# FOTA_LED_Driver.net
KiCad netlist of a schematic drawn in Altium Designer
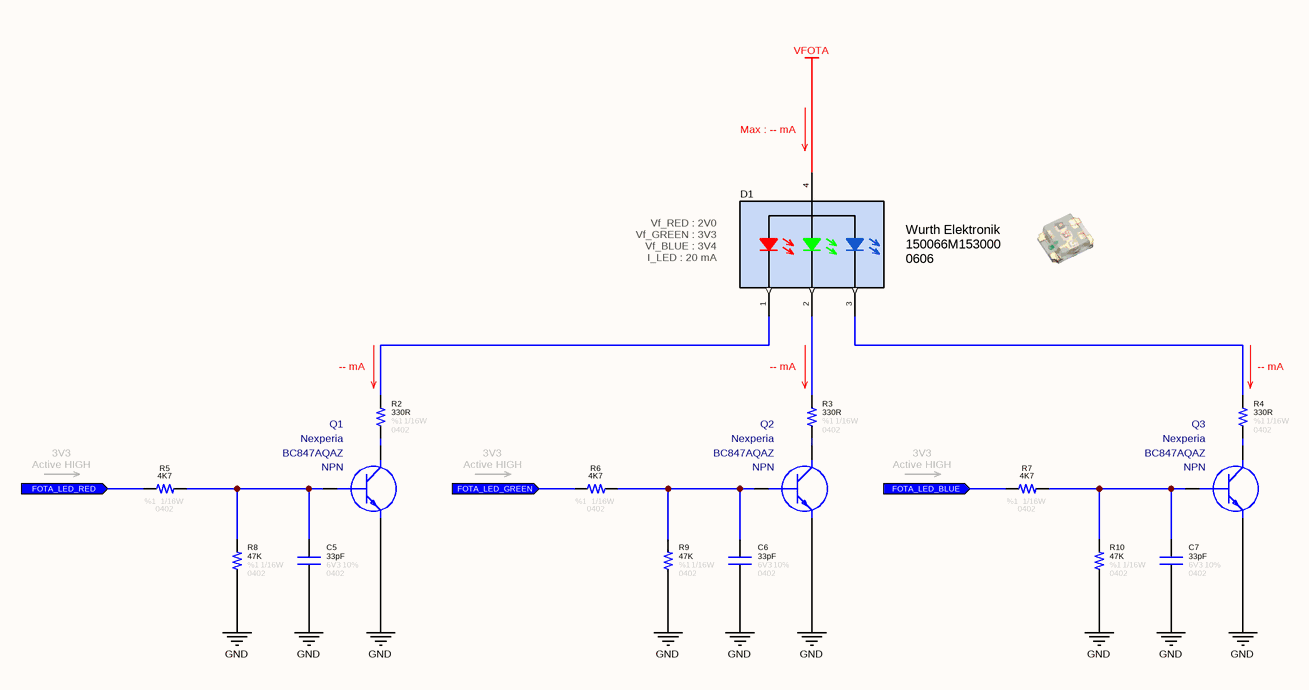
[diagram p0: FOTA LED Driver.SchDoc]

(export (version "E")
  (design (tool "Eeschema 10.0.6"))
  (components
    (comp (ref "C5")
      (value "33pF")
      (footprint "CAPACITOR_0402")
      (description "Capacitor - 33pF [0402] (Ceramic)")
      (fields
        (field (name "MANUFACTURER PART NUMBER") "C0402C330J9RACAUTO")
        (field (name "TOLERANCE") "10%")
        (field (name "CASE") "0402")
        (field (name "VOLTAGE") "6V3")
      )
      (libsource (lib "P101DA_Library") (part "Capacitor - 33pF [0402-6V3]"))
    )
    (comp (ref "C6")
      (value "33pF")
      (footprint "CAPACITOR_0402")
      (description "Capacitor - 33pF [0402] (Ceramic)")
      (fields
        (field (name "MANUFACTURER PART NUMBER") "C0402C330J9RACAUTO")
        (field (name "TOLERANCE") "10%")
        (field (name "CASE") "0402")
        (field (name "VOLTAGE") "6V3")
      )
      (libsource (lib "P101DA_Library") (part "Capacitor - 33pF [0402-6V3]"))
    )
    (comp (ref "C7")
      (value "33pF")
      (footprint "CAPACITOR_0402")
      (description "Capacitor - 33pF [0402] (Ceramic)")
      (fields
        (field (name "MANUFACTURER PART NUMBER") "C0402C330J9RACAUTO")
        (field (name "TOLERANCE") "10%")
        (field (name "CASE") "0402")
        (field (name "VOLTAGE") "6V3")
      )
      (libsource (lib "P101DA_Library") (part "Capacitor - 33pF [0402-6V3]"))
    )
    (comp (ref "D1")
      (value "150066M153000")
      (footprint "Wurth_0606")
      (description "LED RGB DIFFUSED SMD")
      (fields
        (field (name "MANUFACTURER NAME") "Wurth Elektronik")
        (field (name "MANUFACTURER PART NUMBER") "150066M153000")
        (field (name "CASE") "0606")
      )
      (libsource (lib "P101DA_Library") (part "Diode - LED-RGB"))
    )
    (comp (ref "Q1")
      (value "BC847AQAZ")
      (footprint "SOT1215")
      (description "Bipolar NPN Transistors")
      (fields
        (field (name "MANUFACTURER NAME") "Nexperia")
        (field (name "MANUFACTURER PART NUMBER") "BC847AQAZ")
        (field (name "POLARITY") "NPN")
      )
      (libsource (lib "P101DA_Library") (part "Transistor - BC847"))
    )
    (comp (ref "Q2")
      (value "BC847AQAZ")
      (footprint "SOT1215")
      (description "Bipolar NPN Transistors")
      (fields
        (field (name "MANUFACTURER NAME") "Nexperia")
        (field (name "MANUFACTURER PART NUMBER") "BC847AQAZ")
        (field (name "POLARITY") "NPN")
      )
      (libsource (lib "P101DA_Library") (part "Transistor - BC847"))
    )
    (comp (ref "Q3")
      (value "BC847AQAZ")
      (footprint "SOT1215")
      (description "Bipolar NPN Transistors")
      (fields
        (field (name "MANUFACTURER NAME") "Nexperia")
        (field (name "MANUFACTURER PART NUMBER") "BC847AQAZ")
        (field (name "POLARITY") "NPN")
      )
      (libsource (lib "P101DA_Library") (part "Transistor - BC847"))
    )
    (comp (ref "R2")
      (value "330R")
      (footprint "RESISTOR_0402")
      (description "Thick Film Resistors - SMD 1/16 W 330 Ohm 1%")
      (fields
        (field (name "MANUFACTURER PART NUMBER") "CRCW0402330RFKED")
        (field (name "CASE") "0402")
        (field (name "TOLERANCE") "%1")
        (field (name "POWER") "1/16W")
        (field (name "Comment") "330R - 0402 - %1 - 1/16W")
      )
      (libsource (lib "P101DA_Library") (part "Resistor - 330R [0402]"))
    )
    (comp (ref "R3")
      (value "330R")
      (footprint "RESISTOR_0402")
      (description "Thick Film Resistors - SMD 1/16 W 330 Ohm 1%")
      (fields
        (field (name "MANUFACTURER PART NUMBER") "CRCW0402330RFKED")
        (field (name "CASE") "0402")
        (field (name "TOLERANCE") "%1")
        (field (name "POWER") "1/16W")
        (field (name "Comment") "330R - 0402 - %1 - 1/16W")
      )
      (libsource (lib "P101DA_Library") (part "Resistor - 330R [0402]"))
    )
    (comp (ref "R4")
      (value "330R")
      (footprint "RESISTOR_0402")
      (description "Thick Film Resistors - SMD 1/16 W 330 Ohm 1%")
      (fields
        (field (name "MANUFACTURER PART NUMBER") "CRCW0402330RFKED")
        (field (name "CASE") "0402")
        (field (name "TOLERANCE") "%1")
        (field (name "POWER") "1/16W")
        (field (name "Comment") "330R - 0402 - %1 - 1/16W")
      )
      (libsource (lib "P101DA_Library") (part "Resistor - 330R [0402]"))
    )
    (comp (ref "R5")
      (value "4K7")
      (footprint "RESISTOR_0402")
      (description "Thick Film Resistors - SMD 1/16 W 4.7 KOhm 1%")
      (fields
        (field (name "MANUFACTURER PART NUMBER") "CRCW04024K70FKED")
        (field (name "TOLERANCE") "%1")
        (field (name "CASE") "0402")
        (field (name "POWER") "1/16W")
        (field (name "Comment") "4K7 - 0402 - %1 - 1/16W")
      )
      (libsource (lib "P101DA_Library") (part "Resistor - 4K7 [0402]"))
    )
    (comp (ref "R6")
      (value "4K7")
      (footprint "RESISTOR_0402")
      (description "Thick Film Resistors - SMD 1/16 W 4.7 KOhm 1%")
      (fields
        (field (name "MANUFACTURER PART NUMBER") "CRCW04024K70FKED")
        (field (name "TOLERANCE") "%1")
        (field (name "CASE") "0402")
        (field (name "POWER") "1/16W")
        (field (name "Comment") "4K7 - 0402 - %1 - 1/16W")
      )
      (libsource (lib "P101DA_Library") (part "Resistor - 4K7 [0402]"))
    )
    (comp (ref "R7")
      (value "4K7")
      (footprint "RESISTOR_0402")
      (description "Thick Film Resistors - SMD 1/16 W 4.7 KOhm 1%")
      (fields
        (field (name "MANUFACTURER PART NUMBER") "CRCW04024K70FKED")
        (field (name "TOLERANCE") "%1")
        (field (name "CASE") "0402")
        (field (name "POWER") "1/16W")
        (field (name "Comment") "4K7 - 0402 - %1 - 1/16W")
      )
      (libsource (lib "P101DA_Library") (part "Resistor - 4K7 [0402]"))
    )
    (comp (ref "R8")
      (value "47K")
      (footprint "RESISTOR_0402")
      (description "Thick Film Resistors - SMD 1/16 W 47 KOhm 1%")
      (fields
        (field (name "MANUFACTURER PART NUMBER") "CRCW040247K0FKED")
        (field (name "TOLERANCE") "%1")
        (field (name "CASE") "0402")
        (field (name "POWER") "1/16W")
        (field (name "Comment") "47K - 0402 - %1 - 1/16W")
      )
      (libsource (lib "P101DA_Library") (part "Resistor - 47K [0402]"))
    )
    (comp (ref "R9")
      (value "47K")
      (footprint "RESISTOR_0402")
      (description "Thick Film Resistors - SMD 1/16 W 47 KOhm 1%")
      (fields
        (field (name "MANUFACTURER PART NUMBER") "CRCW040247K0FKED")
        (field (name "TOLERANCE") "%1")
        (field (name "CASE") "0402")
        (field (name "POWER") "1/16W")
        (field (name "Comment") "47K - 0402 - %1 - 1/16W")
      )
      (libsource (lib "P101DA_Library") (part "Resistor - 47K [0402]"))
    )
    (comp (ref "R10")
      (value "47K")
      (footprint "RESISTOR_0402")
      (description "Thick Film Resistors - SMD 1/16 W 47 KOhm 1%")
      (fields
        (field (name "MANUFACTURER PART NUMBER") "CRCW040247K0FKED")
        (field (name "TOLERANCE") "%1")
        (field (name "CASE") "0402")
        (field (name "POWER") "1/16W")
        (field (name "Comment") "47K - 0402 - %1 - 1/16W")
      )
      (libsource (lib "P101DA_Library") (part "Resistor - 47K [0402]"))
    )
  )
  (nets
    (net (code "1") (name "/FOTA_LED_BLUE") (class "Default")
      (node (ref "R7") (pin "2") (pinfunction "2_2") (pintype "passive"))
    )
    (net (code "2") (name "/FOTA_LED_GREEN") (class "Default")
      (node (ref "R6") (pin "2") (pinfunction "2_2") (pintype "passive"))
    )
    (net (code "3") (name "/FOTA_LED_RED") (class "Default")
      (node (ref "R5") (pin "2") (pinfunction "2_2") (pintype "passive"))
    )
    (net (code "4") (name "GND") (class "Default")
      (node (ref "C5") (pin "1") (pinfunction "1_1") (pintype "passive"))
      (node (ref "C6") (pin "1") (pinfunction "1_1") (pintype "passive"))
      (node (ref "C7") (pin "1") (pinfunction "1_1") (pintype "passive"))
      (node (ref "Q1") (pin "2") (pinfunction "E_2") (pintype "passive"))
      (node (ref "Q2") (pin "2") (pinfunction "E_2") (pintype "passive"))
      (node (ref "Q3") (pin "2") (pinfunction "E_2") (pintype "passive"))
      (node (ref "R10") (pin "1") (pinfunction "1_1") (pintype "passive"))
      (node (ref "R8") (pin "1") (pinfunction "1_1") (pintype "passive"))
      (node (ref "R9") (pin "1") (pinfunction "1_1") (pintype "passive"))
    )
    (net (code "5") (name "Net-(D1-Pad1)") (class "Default")
      (node (ref "D1") (pin "1") (pinfunction "1_1") (pintype "output"))
      (node (ref "R2") (pin "2") (pinfunction "2_2") (pintype "passive"))
    )
    (net (code "6") (name "Net-(D1-Pad2)") (class "Default")
      (node (ref "D1") (pin "2") (pinfunction "2_2") (pintype "output"))
      (node (ref "R3") (pin "2") (pinfunction "2_2") (pintype "passive"))
    )
    (net (code "7") (name "Net-(D1-Pad3)") (class "Default")
      (node (ref "D1") (pin "3") (pinfunction "3_3") (pintype "output"))
      (node (ref "R4") (pin "2") (pinfunction "2_2") (pintype "passive"))
    )
    (net (code "8") (name "Net-(Q1-B)") (class "Default")
      (node (ref "C5") (pin "2") (pinfunction "2_2") (pintype "passive"))
      (node (ref "Q1") (pin "1") (pinfunction "B_1") (pintype "passive"))
      (node (ref "R5") (pin "1") (pinfunction "1_1") (pintype "passive"))
      (node (ref "R8") (pin "2") (pinfunction "2_2") (pintype "passive"))
    )
    (net (code "9") (name "Net-(Q1-C)") (class "Default")
      (node (ref "Q1") (pin "3") (pinfunction "C_3") (pintype "passive"))
      (node (ref "R2") (pin "1") (pinfunction "1_1") (pintype "passive"))
    )
    (net (code "10") (name "Net-(Q2-B)") (class "Default")
      (node (ref "C6") (pin "2") (pinfunction "2_2") (pintype "passive"))
      (node (ref "Q2") (pin "1") (pinfunction "B_1") (pintype "passive"))
      (node (ref "R6") (pin "1") (pinfunction "1_1") (pintype "passive"))
      (node (ref "R9") (pin "2") (pinfunction "2_2") (pintype "passive"))
    )
    (net (code "11") (name "Net-(Q2-C)") (class "Default")
      (node (ref "Q2") (pin "3") (pinfunction "C_3") (pintype "passive"))
      (node (ref "R3") (pin "1") (pinfunction "1_1") (pintype "passive"))
    )
    (net (code "12") (name "Net-(Q3-B)") (class "Default")
      (node (ref "C7") (pin "2") (pinfunction "2_2") (pintype "passive"))
      (node (ref "Q3") (pin "1") (pinfunction "B_1") (pintype "passive"))
      (node (ref "R10") (pin "2") (pinfunction "2_2") (pintype "passive"))
      (node (ref "R7") (pin "1") (pinfunction "1_1") (pintype "passive"))
    )
    (net (code "13") (name "Net-(Q3-C)") (class "Default")
      (node (ref "Q3") (pin "3") (pinfunction "C_3") (pintype "passive"))
      (node (ref "R4") (pin "1") (pinfunction "1_1") (pintype "passive"))
    )
    (net (code "14") (name "VFOTA") (class "Default")
      (node (ref "D1") (pin "4") (pinfunction "4_4") (pintype "power_in"))
    )
  )
)
